# Adapter.net
KiCad netlist of a schematic drawn in Altium Designer
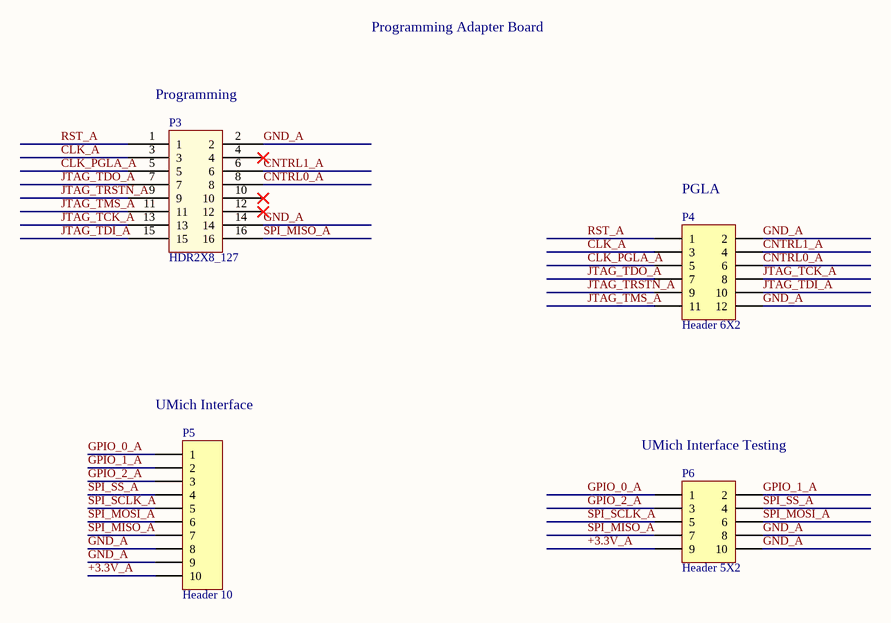
[diagram p0: Adapter.SchDoc]

(export (version "E")
  (design (tool "Eeschema 10.0.6"))
  (components
    (comp (ref "P3")
      (value "HDR2X8_127")
      (footprint "HDR2X8_127")
      (description "Header 16 positions 1.27mm")
      (libsource (lib "INERTIA") (part "HDR2X8_127"))
    )
    (comp (ref "P4")
      (value "Header 6X2")
      (footprint "HDR2X6")
      (description "Header, 6-Pin, Dual row")
      (fields (field (name "PUBLISHER") "Altium Limited"))
      (libsource (lib "Miscellaneous Connectors") (part "Header 6X2"))
    )
    (comp (ref "P5")
      (value "Header 10")
      (footprint "505110-1092")
      (description "Header, 10-Pin")
      (fields (field (name "PUBLISHER") "Altium Limited"))
      (libsource (lib "Miscellaneous Connectors") (part "Header 10"))
    )
    (comp (ref "P6")
      (value "Header 5X2")
      (footprint "HDR2X5")
      (description "Header, 5-Pin, Dual row")
      (fields (field (name "PUBLISHER") "Altium Limited"))
      (libsource (lib "Miscellaneous Connectors") (part "Header 5X2"))
    )
  )
  (nets
    (net (code "1") (name "/+3.3V_A") (class "Default")
      (node (ref "P5") (pin "10") (pinfunction "10_10") (pintype "passive"))
      (node (ref "P6") (pin "9") (pinfunction "9_9") (pintype "passive"))
    )
    (net (code "2") (name "/CLK_A") (class "Default")
      (node (ref "P3") (pin "3") (pinfunction "3_3") (pintype "passive"))
      (node (ref "P4") (pin "3") (pinfunction "3_3") (pintype "passive"))
    )
    (net (code "3") (name "/CLK_PGLA_A") (class "Default")
      (node (ref "P3") (pin "5") (pinfunction "5_5") (pintype "passive"))
      (node (ref "P4") (pin "5") (pinfunction "5_5") (pintype "passive"))
    )
    (net (code "4") (name "/CNTRL0_A") (class "Default")
      (node (ref "P3") (pin "8") (pinfunction "8_8") (pintype "passive"))
      (node (ref "P4") (pin "6") (pinfunction "6_6") (pintype "passive"))
    )
    (net (code "5") (name "/CNTRL1_A") (class "Default")
      (node (ref "P3") (pin "6") (pinfunction "6_6") (pintype "passive"))
      (node (ref "P4") (pin "4") (pinfunction "4_4") (pintype "passive"))
    )
    (net (code "6") (name "/GND_A") (class "Default")
      (node (ref "P3") (pin "14") (pinfunction "14_14") (pintype "passive"))
      (node (ref "P3") (pin "2") (pinfunction "2_2") (pintype "passive"))
      (node (ref "P4") (pin "12") (pinfunction "12_12") (pintype "passive"))
      (node (ref "P4") (pin "2") (pinfunction "2_2") (pintype "passive"))
      (node (ref "P5") (pin "8") (pinfunction "8_8") (pintype "passive"))
      (node (ref "P5") (pin "9") (pinfunction "9_9") (pintype "passive"))
      (node (ref "P6") (pin "10") (pinfunction "10_10") (pintype "passive"))
      (node (ref "P6") (pin "8") (pinfunction "8_8") (pintype "passive"))
    )
    (net (code "7") (name "/GPIO_0_A") (class "Default")
      (node (ref "P5") (pin "1") (pinfunction "1_1") (pintype "passive"))
      (node (ref "P6") (pin "1") (pinfunction "1_1") (pintype "passive"))
    )
    (net (code "8") (name "/GPIO_1_A") (class "Default")
      (node (ref "P5") (pin "2") (pinfunction "2_2") (pintype "passive"))
      (node (ref "P6") (pin "2") (pinfunction "2_2") (pintype "passive"))
    )
    (net (code "9") (name "/GPIO_2_A") (class "Default")
      (node (ref "P5") (pin "3") (pinfunction "3_3") (pintype "passive"))
      (node (ref "P6") (pin "3") (pinfunction "3_3") (pintype "passive"))
    )
    (net (code "10") (name "/JTAG_TCK_A") (class "Default")
      (node (ref "P3") (pin "13") (pinfunction "13_13") (pintype "passive"))
      (node (ref "P4") (pin "8") (pinfunction "8_8") (pintype "passive"))
    )
    (net (code "11") (name "/JTAG_TDI_A") (class "Default")
      (node (ref "P3") (pin "15") (pinfunction "15_15") (pintype "passive"))
      (node (ref "P4") (pin "10") (pinfunction "10_10") (pintype "passive"))
    )
    (net (code "12") (name "/JTAG_TDO_A") (class "Default")
      (node (ref "P3") (pin "7") (pinfunction "7_7") (pintype "passive"))
      (node (ref "P4") (pin "7") (pinfunction "7_7") (pintype "passive"))
    )
    (net (code "13") (name "/JTAG_TMS_A") (class "Default")
      (node (ref "P3") (pin "11") (pinfunction "11_11") (pintype "passive"))
      (node (ref "P4") (pin "11") (pinfunction "11_11") (pintype "passive"))
    )
    (net (code "14") (name "/JTAG_TRSTN_A") (class "Default")
      (node (ref "P3") (pin "9") (pinfunction "9_9") (pintype "passive"))
      (node (ref "P4") (pin "9") (pinfunction "9_9") (pintype "passive"))
    )
    (net (code "15") (name "/RST_A") (class "Default")
      (node (ref "P3") (pin "1") (pinfunction "1_1") (pintype "passive"))
      (node (ref "P4") (pin "1") (pinfunction "1_1") (pintype "passive"))
    )
    (net (code "16") (name "/SPI_MISO_A") (class "Default")
      (node (ref "P3") (pin "16") (pinfunction "16_16") (pintype "passive"))
      (node (ref "P5") (pin "7") (pinfunction "7_7") (pintype "passive"))
      (node (ref "P6") (pin "7") (pinfunction "7_7") (pintype "passive"))
    )
    (net (code "17") (name "/SPI_MOSI_A") (class "Default")
      (node (ref "P5") (pin "6") (pinfunction "6_6") (pintype "passive"))
      (node (ref "P6") (pin "6") (pinfunction "6_6") (pintype "passive"))
    )
    (net (code "18") (name "/SPI_SCLK_A") (class "Default")
      (node (ref "P5") (pin "5") (pinfunction "5_5") (pintype "passive"))
      (node (ref "P6") (pin "5") (pinfunction "5_5") (pintype "passive"))
    )
    (net (code "19") (name "/SPI_SS_A") (class "Default")
      (node (ref "P5") (pin "4") (pinfunction "4_4") (pintype "passive"))
      (node (ref "P6") (pin "4") (pinfunction "4_4") (pintype "passive"))
    )
    (net (code "20") (name "unconnected-(P3-Pad4)") (class "Default")
      (node (ref "P3") (pin "4") (pinfunction "4_4") (pintype "passive+no_connect"))
    )
    (net (code "21") (name "unconnected-(P3-Pad10)") (class "Default")
      (node (ref "P3") (pin "10") (pinfunction "10_10") (pintype "passive+no_connect"))
    )
    (net (code "22") (name "unconnected-(P3-Pad12)") (class "Default")
      (node (ref "P3") (pin "12") (pinfunction "12_12") (pintype "passive+no_connect"))
    )
  )
)
